# MP8756GD.net
KiCad netlist of a schematic drawn in Altium Designer
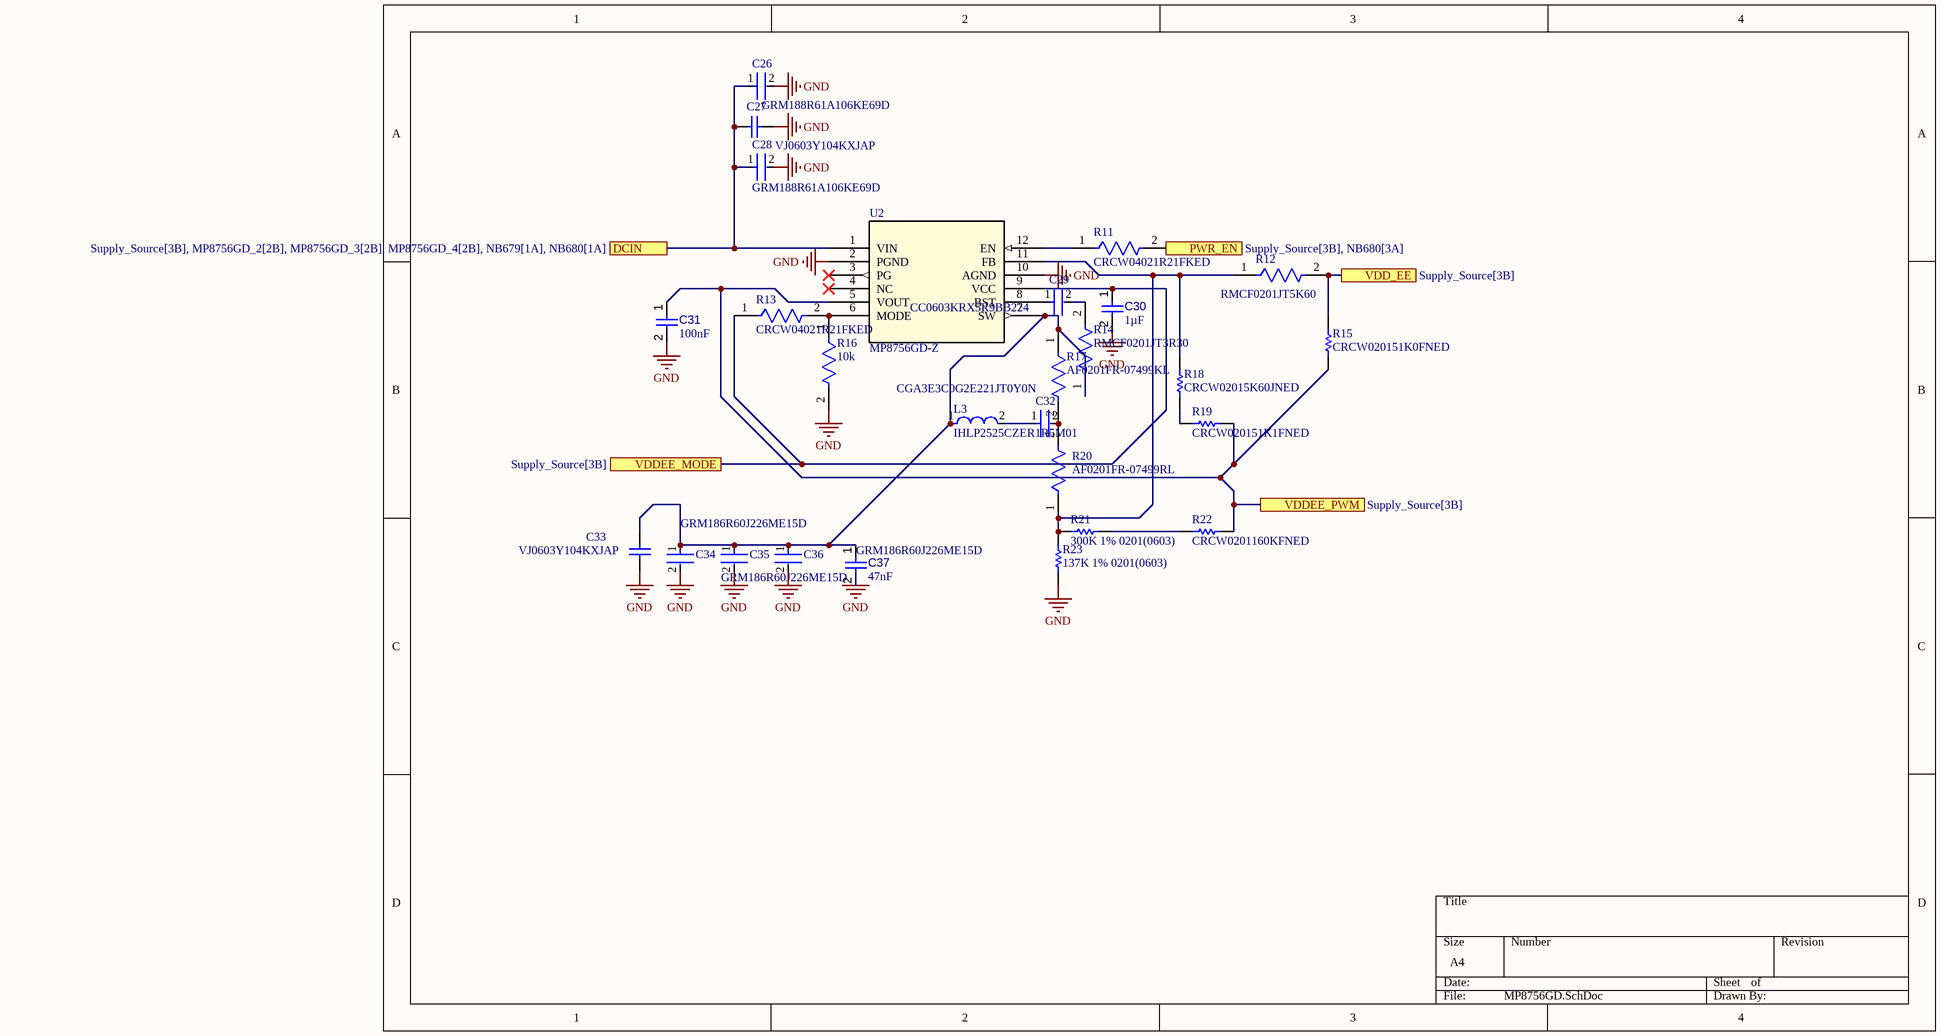
[diagram p0: MP8756GD.SchDoc]

(export (version "E")
  (design (tool "Eeschema 10.0.6"))
  (components
    (comp (ref "C26")
      (value "GRM188R61A106KE69D")
      (footprint "FP-GRM18-0_15-MFG")
      (description "CAP CER 10UF 10V X5R 0603")
      (fields
        (field (name "OCTOPART") "https://octopart.com/grm188r61a106ke69d-murata-22851381")
        (field (name "MANUFACTURER") "Murata")
      )
      (libsource (lib "Altium Content Vault") (part "11868f565c42a9108669ba33697ecf6"))
    )
    (comp (ref "C27")
      (value "VJ0603Y104KXJAP")
      (footprint "CAPC1608X92X38NL15T08")
      (fields (field (name "MANUFACTURER") "Vitramon"))
      (libsource (lib "Altium Content Vault") (part "CAP"))
    )
    (comp (ref "C28")
      (value "GRM188R61A106KE69D")
      (footprint "FP-GRM18-0_15-MFG")
      (description "CAP CER 10UF 10V X5R 0603")
      (fields
        (field (name "OCTOPART") "https://octopart.com/grm188r61a106ke69d-murata-22851381")
        (field (name "MANUFACTURER") "Murata")
      )
      (libsource (lib "Altium Content Vault") (part "11868f565c42a9108669ba33697ecf6"))
    )
    (comp (ref "C29")
      (value "CC0603KRX5R9BB224")
      (footprint "FP-CC0603-DA-MFG")
      (description "CC0603 220 nF X5R 10.00% 50 V")
      (fields
        (field (name "TOLERANCE") "0.1")
        (field (name "OCTOPART") "https://octopart.com/cc0603krx5r9bb224-yageo-90326743")
      )
      (libsource (lib "Altium Content Vault") (part "11868f565c42a9108669ba33697ecf6"))
    )
    (comp (ref "C30")
      (value "1µF")
      (footprint "CAPC1005X55X25LL05T10")
      (description "Chip Capacitor, 1 uF, +/- 10%, 6.3 V, 0402 (1005 Metric)")
      (fields (field (name "TOLERANCE") "10%") (field (name "Comment") "Capacitor 1 uF +/- 10% 6.3 V 0402"))
      (libsource (lib "MIGUEL ANGEL ALVAREZ GUZMAN") (part "CAP-NP-2"))
    )
    (comp (ref "C31")
      (value "100nF")
      (footprint "CAPC1005X56X25LL10T15")
      (description "Chip Capacitor, 0.1 uF, +/- 5%, 16 V, 0402 (1005 Metric)")
      (fields (field (name "TOLERANCE") "5%") (field (name "Comment") "Capacitor 0.1 uF +/- 5% 16 V 0402"))
      (libsource (lib "MIGUEL ANGEL ALVAREZ GUZMAN") (part "CAP-NP-2"))
    )
    (comp (ref "C32")
      (value "CGA3E3C0G2E221JT0Y0N")
      (footprint "FP-CGA3E-0_3-0_1-IPC_B")
      (description "Cap Ceramic 220pF 250V C0G 5% Pad SMD 0603 +125°C Automotive T/R")
      (libsource (lib "Altium Content Vault") (part "b4654b650e69147ec39a6b967a45e02"))
    )
    (comp (ref "C33")
      (value "VJ0603Y104KXJAP")
      (footprint "CAPC1608X92X38NL15T08")
      (fields (field (name "MANUFACTURER") "Vitramon"))
      (libsource (lib "Altium Content Vault") (part "CAP"))
    )
    (comp (ref "C34")
      (value "GRM186R60J226ME15D")
      (footprint "FP-GRM186-0_2-IPC_B")
      (description "Chip Multilayer Ceramic Capacitors for General Purpose, 0603, 22uF, X5R, 15%, 20%, 6.3V")
      (fields (field (name "TOLERANCE") "20%"))
      (libsource (lib "Altium Content Vault") (part "02cd4be3c70576c341d710602a673aa"))
    )
    (comp (ref "C35")
      (value "GRM186R60J226ME15D")
      (footprint "FP-GRM186-0_2-IPC_B")
      (description "Chip Multilayer Ceramic Capacitors for General Purpose, 0603, 22uF, X5R, 15%, 20%, 6.3V")
      (fields (field (name "TOLERANCE") "20%"))
      (libsource (lib "Altium Content Vault") (part "02cd4be3c70576c341d710602a673aa"))
    )
    (comp (ref "C36")
      (value "GRM186R60J226ME15D")
      (footprint "FP-GRM186-0_2-IPC_B")
      (description "Chip Multilayer Ceramic Capacitors for General Purpose, 0603, 22uF, X5R, 15%, 20%, 6.3V")
      (fields (field (name "TOLERANCE") "20%"))
      (libsource (lib "Altium Content Vault") (part "02cd4be3c70576c341d710602a673aa"))
    )
    (comp (ref "C37")
      (value "47nF")
      (footprint "CAPC0402(1005)60_L")
      (description "Chip Capacitor, 47nF +/-20%, 50V, 0402, Thickness 0.6 mm")
      (fields (field (name "TOLERANCE") "20%") (field (name "Comment") "Capacitor 47nF +/-20% 50V 0402"))
      (libsource (lib "MIGUEL ANGEL ALVAREZ GUZMAN") (part "CAP-NP-2"))
    )
    (comp (ref "L3")
      (value "IHLP2525CZER1R5M01")
      (footprint "FP-IHLP-2525CZ-FP_2_413x3-MFG")
      (description "Commercial Inductors, High Saturation Series 1.5uH 9A 15mΩ 20%")
      (fields (field (name "TOLERANCE") "20%"))
      (libsource (lib "Altium Content Vault") (part "725321dda6339637d4d059423bc1c3c"))
    )
    (comp (ref "R11")
      (value "CRCW04021R21FKED")
      (footprint "FP-CRCW0402-e3-MFG")
      (description "RES Thick Film, 1.21Ω, 1%, 0.063W, 100ppm/°C, 0402")
      (fields (field (name "TOLERANCE") "1%"))
      (libsource (lib "Altium Content Vault") (part "1029c3af85768c4190bb7ad29bc67b5"))
    )
    (comp (ref "R12")
      (value "RMCF0201JT5K60")
      (footprint "FP-RMCF0201-MFG")
      (description "5.6kΩ ±5% 0.05W 0201 Thick Film Chip Resistor AEC-Q200 compliant")
      (fields (field (name "TOLERANCE") "5%"))
      (libsource (lib "Altium Content Vault") (part "1029c3af85768c4190bb7ad29bc67b5"))
    )
    (comp (ref "R13")
      (value "CRCW04021R21FKED")
      (footprint "FP-CRCW0402-e3-MFG")
      (description "RES Thick Film, 1.21Ω, 1%, 0.063W, 100ppm/°C, 0402")
      (fields (field (name "TOLERANCE") "1%"))
      (libsource (lib "Altium Content Vault") (part "1029c3af85768c4190bb7ad29bc67b5"))
    )
    (comp (ref "R14")
      (value "RMCF0201JT3R30")
      (footprint "FP-RMCF0201-IPC_A")
      (description "3.3Ω ±5% 0.05W 0201 Thick Film Chip Resistor AEC-Q200 compliant")
      (fields (field (name "TOLERANCE") "5%"))
      (libsource (lib "Altium Content Vault") (part "1029c3af85768c4190bb7ad29bc67b5"))
    )
    (comp (ref "R15")
      (value "CRCW020151K0FNED")
      (footprint "RESC0603X28X15LL05T05")
      (fields (field (name "MANUFACTURER") "Vishay Dale"))
      (libsource (lib "Altium Content Vault") (part "RES"))
    )
    (comp (ref "R16")
      (value "10k")
      (footprint "FP-RT0201-IPC_C")
      (description "Fixed Resistor, Thin Film, 0.05W, 10000ohm, 25V, 0.1% +/-Tol, 50ppm/Cel, Surface Mount, 0201")
      (fields (field (name "TOLERANCE") "0.1%") (field (name "Comment") "RT0201BRE0710KL"))
      (libsource (lib "MIGUEL ANGEL ALVAREZ GUZMAN") (part "1029c3af85768c4190bb7ad29bc67b5"))
    )
    (comp (ref "R17")
      (value "AF0201FR-07499KL")
      (footprint "FP-AF0201-MFG")
      (description "Anti-Sulfurated Chip Resistors Automotive Grade 499kΩ 1% 200ppm/°C 0201")
      (fields (field (name "TOLERANCE") "1%"))
      (libsource (lib "Altium Content Vault") (part "1029c3af85768c4190bb7ad29bc67b5"))
    )
    (comp (ref "R18")
      (value "CRCW02015K60JNED")
      (footprint "RESC0603X28X15NL05T05")
      (fields (field (name "MANUFACTURER") "Vishay Dale"))
      (libsource (lib "Altium Content Vault") (part "RES"))
    )
    (comp (ref "R19")
      (value "CRCW020151K1FNED")
      (footprint "RESC0603X28X15ML05T05")
      (fields (field (name "MANUFACTURER") "Vishay Dale"))
      (libsource (lib "Altium Content Vault") (part "RES"))
    )
    (comp (ref "R20")
      (value "AF0201FR-07499RL")
      (footprint "FP-AF0201-IPC_A")
      (description "Anti-Sulfurated Chip Resistors Automotive Grade 499Ω 1% 200ppm/°C 0201")
      (fields (field (name "TOLERANCE") "1%"))
      (libsource (lib "Altium Content Vault") (part "1029c3af85768c4190bb7ad29bc67b5"))
    )
    (comp (ref "R21")
      (value "300K 1% 0201(0603)")
      (footprint "RESC0201(0603)_L")
      (description "300K 0.05W 1% 0201 (0603 Metric)  SMD")
      (fields (field (name "POWER") "0.05 W") (field (name "TOLERANCE") "1 %"))
      (libsource (lib "Altium Content Vault") (part "RES"))
    )
    (comp (ref "R22")
      (value "CRCW0201160KFNED")
      (footprint "RESC0603X28X15ML05T05")
      (fields (field (name "MANUFACTURER") "Vishay Dale"))
      (libsource (lib "Altium Content Vault") (part "RES"))
    )
    (comp (ref "R23")
      (value "137K 1% 0201(0603)")
      (footprint "RESC0201(0603)_M")
      (description "137K 0.05W 1% 0201 (0603 Metric)  SMD")
      (fields (field (name "POWER") "0.05 W") (field (name "TOLERANCE") "1 %"))
      (libsource (lib "Altium Content Vault") (part "RES"))
    )
    (comp (ref "U2")
      (value "MP8756GD-Z")
      (footprint "QFN-12_MP8756_MNP")
      (description "26V 6A Low IQ High-Current Synchronous Step-Down Converter")
      (fields (field (name "COPYRIGHT") "Copyright (C) 2025 Ultra Librarian. All rights reserved."))
      (libsource (lib "MIGUEL ANGEL ALVAREZ GUZMAN") (part "MP8756GD-Z"))
    )
  )
  (nets
    (net (code "1") (name "/DCIN") (class "Default")
      (node (ref "C26") (pin "1") (pinfunction "1_1") (pintype "passive"))
      (node (ref "C27") (pin "2") (pinfunction "2_2") (pintype "passive"))
      (node (ref "C28") (pin "1") (pinfunction "1_1") (pintype "passive"))
      (node (ref "U2") (pin "1") (pinfunction "VIN_1") (pintype "power_in"))
    )
    (net (code "2") (name "/PWR_EN") (class "Default")
      (node (ref "R11") (pin "2") (pinfunction "2_2") (pintype "passive"))
    )
    (net (code "3") (name "/VDDEE_MODE") (class "Default")
      (node (ref "C30") (pin "1") (pinfunction "1_1") (pintype "passive"))
      (node (ref "R13") (pin "1") (pinfunction "1_1") (pintype "passive"))
      (node (ref "U2") (pin "9") (pinfunction "VCC_9") (pintype "power_in"))
    )
    (net (code "4") (name "/VDDEE_PWM") (class "Default")
      (node (ref "C31") (pin "1") (pinfunction "1_1") (pintype "passive"))
      (node (ref "R15") (pin "2") (pinfunction "2_2") (pintype "passive"))
      (node (ref "R19") (pin "2") (pinfunction "2_2") (pintype "passive"))
      (node (ref "R22") (pin "2") (pinfunction "2_2") (pintype "passive"))
      (node (ref "U2") (pin "5") (pinfunction "VOUT_5") (pintype "power_in"))
    )
    (net (code "5") (name "/VDD_EE") (class "Default")
      (node (ref "R12") (pin "2") (pinfunction "2_2") (pintype "passive"))
      (node (ref "R15") (pin "1") (pinfunction "1_1") (pintype "passive"))
    )
    (net (code "6") (name "GND") (class "Default")
      (node (ref "C26") (pin "2") (pinfunction "2_2") (pintype "passive"))
      (node (ref "C27") (pin "1") (pinfunction "1_1") (pintype "passive"))
      (node (ref "C28") (pin "2") (pinfunction "2_2") (pintype "passive"))
      (node (ref "C30") (pin "2") (pinfunction "2_2") (pintype "passive"))
      (node (ref "C31") (pin "2") (pinfunction "2_2") (pintype "passive"))
      (node (ref "C33") (pin "1") (pinfunction "1_1") (pintype "passive"))
      (node (ref "C34") (pin "2") (pinfunction "2_2") (pintype "passive"))
      (node (ref "C35") (pin "2") (pinfunction "2_2") (pintype "passive"))
      (node (ref "C36") (pin "2") (pinfunction "2_2") (pintype "passive"))
      (node (ref "C37") (pin "2") (pinfunction "2_2") (pintype "passive"))
      (node (ref "R16") (pin "2") (pinfunction "2_2") (pintype "passive"))
      (node (ref "R23") (pin "1") (pinfunction "1_1") (pintype "passive"))
      (node (ref "U2") (pin "10") (pinfunction "AGND_10") (pintype "power_in"))
      (node (ref "U2") (pin "2") (pinfunction "PGND_2") (pintype "power_in"))
    )
    (net (code "7") (name "Net-(C29-Pad2)") (class "Default")
      (node (ref "C29") (pin "2") (pinfunction "2_2") (pintype "passive"))
      (node (ref "R14") (pin "2") (pinfunction "2_2") (pintype "passive"))
    )
    (net (code "8") (name "Net-(C32-Pad1)") (class "Default")
      (node (ref "C32") (pin "1") (pinfunction "1_1") (pintype "passive"))
      (node (ref "L3") (pin "2") (pinfunction "2_2") (pintype "passive"))
    )
    (net (code "9") (name "Net-(C32-Pad2)") (class "Default")
      (node (ref "C32") (pin "2") (pinfunction "2_2") (pintype "passive"))
      (node (ref "R17") (pin "2") (pinfunction "2_2") (pintype "passive"))
      (node (ref "R20") (pin "2") (pinfunction "2_2") (pintype "passive"))
    )
    (net (code "10") (name "Net-(R18-Pad2)") (class "Default")
      (node (ref "R18") (pin "2") (pinfunction "2_2") (pintype "passive"))
      (node (ref "R19") (pin "1") (pinfunction "1_1") (pintype "passive"))
    )
    (net (code "11") (name "Net-(R21-Pad2)") (class "Default")
      (node (ref "R21") (pin "2") (pinfunction "2_2") (pintype "passive"))
      (node (ref "R22") (pin "1") (pinfunction "1_1") (pintype "passive"))
    )
    (net (code "12") (name "Net-(U2-BST)") (class "Default")
      (node (ref "C29") (pin "1") (pinfunction "1_1") (pintype "passive"))
      (node (ref "U2") (pin "8") (pinfunction "BST_8") (pintype "power_in"))
    )
    (net (code "13") (name "Net-(U2-EN)") (class "Default")
      (node (ref "R11") (pin "1") (pinfunction "1_1") (pintype "passive"))
      (node (ref "U2") (pin "12") (pinfunction "EN_12") (pintype "input"))
    )
    (net (code "14") (name "Net-(U2-FB)") (class "Default")
      (node (ref "R12") (pin "1") (pinfunction "1_1") (pintype "passive"))
      (node (ref "R18") (pin "1") (pinfunction "1_1") (pintype "passive"))
      (node (ref "R20") (pin "1") (pinfunction "1_1") (pintype "passive"))
      (node (ref "R21") (pin "1") (pinfunction "1_1") (pintype "passive"))
      (node (ref "R23") (pin "2") (pinfunction "2_2") (pintype "passive"))
      (node (ref "U2") (pin "11") (pinfunction "FB_11") (pintype "passive"))
    )
    (net (code "15") (name "Net-(U2-MODE)") (class "Default")
      (node (ref "R13") (pin "2") (pinfunction "2_2") (pintype "passive"))
      (node (ref "R16") (pin "1") (pinfunction "1_1") (pintype "passive"))
      (node (ref "U2") (pin "6") (pinfunction "MODE_6") (pintype "passive"))
    )
    (net (code "16") (name "Net-(U2-SW)") (class "Default")
      (node (ref "C33") (pin "2") (pinfunction "2_2") (pintype "passive"))
      (node (ref "C34") (pin "1") (pinfunction "1_1") (pintype "passive"))
      (node (ref "C35") (pin "1") (pinfunction "1_1") (pintype "passive"))
      (node (ref "C36") (pin "1") (pinfunction "1_1") (pintype "passive"))
      (node (ref "C37") (pin "1") (pinfunction "1_1") (pintype "passive"))
      (node (ref "L3") (pin "1") (pinfunction "1_1") (pintype "passive"))
      (node (ref "R14") (pin "1") (pinfunction "1_1") (pintype "passive"))
      (node (ref "R17") (pin "1") (pinfunction "1_1") (pintype "passive"))
      (node (ref "U2") (pin "7") (pinfunction "SW_7") (pintype "output"))
    )
    (net (code "17") (name "unconnected-(U2-NC-Pad4)") (class "Default")
      (node (ref "U2") (pin "4") (pinfunction "NC_4") (pintype "passive+no_connect"))
    )
    (net (code "18") (name "unconnected-(U2-PG-Pad3)") (class "Default")
      (node (ref "U2") (pin "3") (pinfunction "PG_3") (pintype "output+no_connect"))
    )
  )
)
